# dac.net
KiCad netlist of a schematic drawn in EAGLE
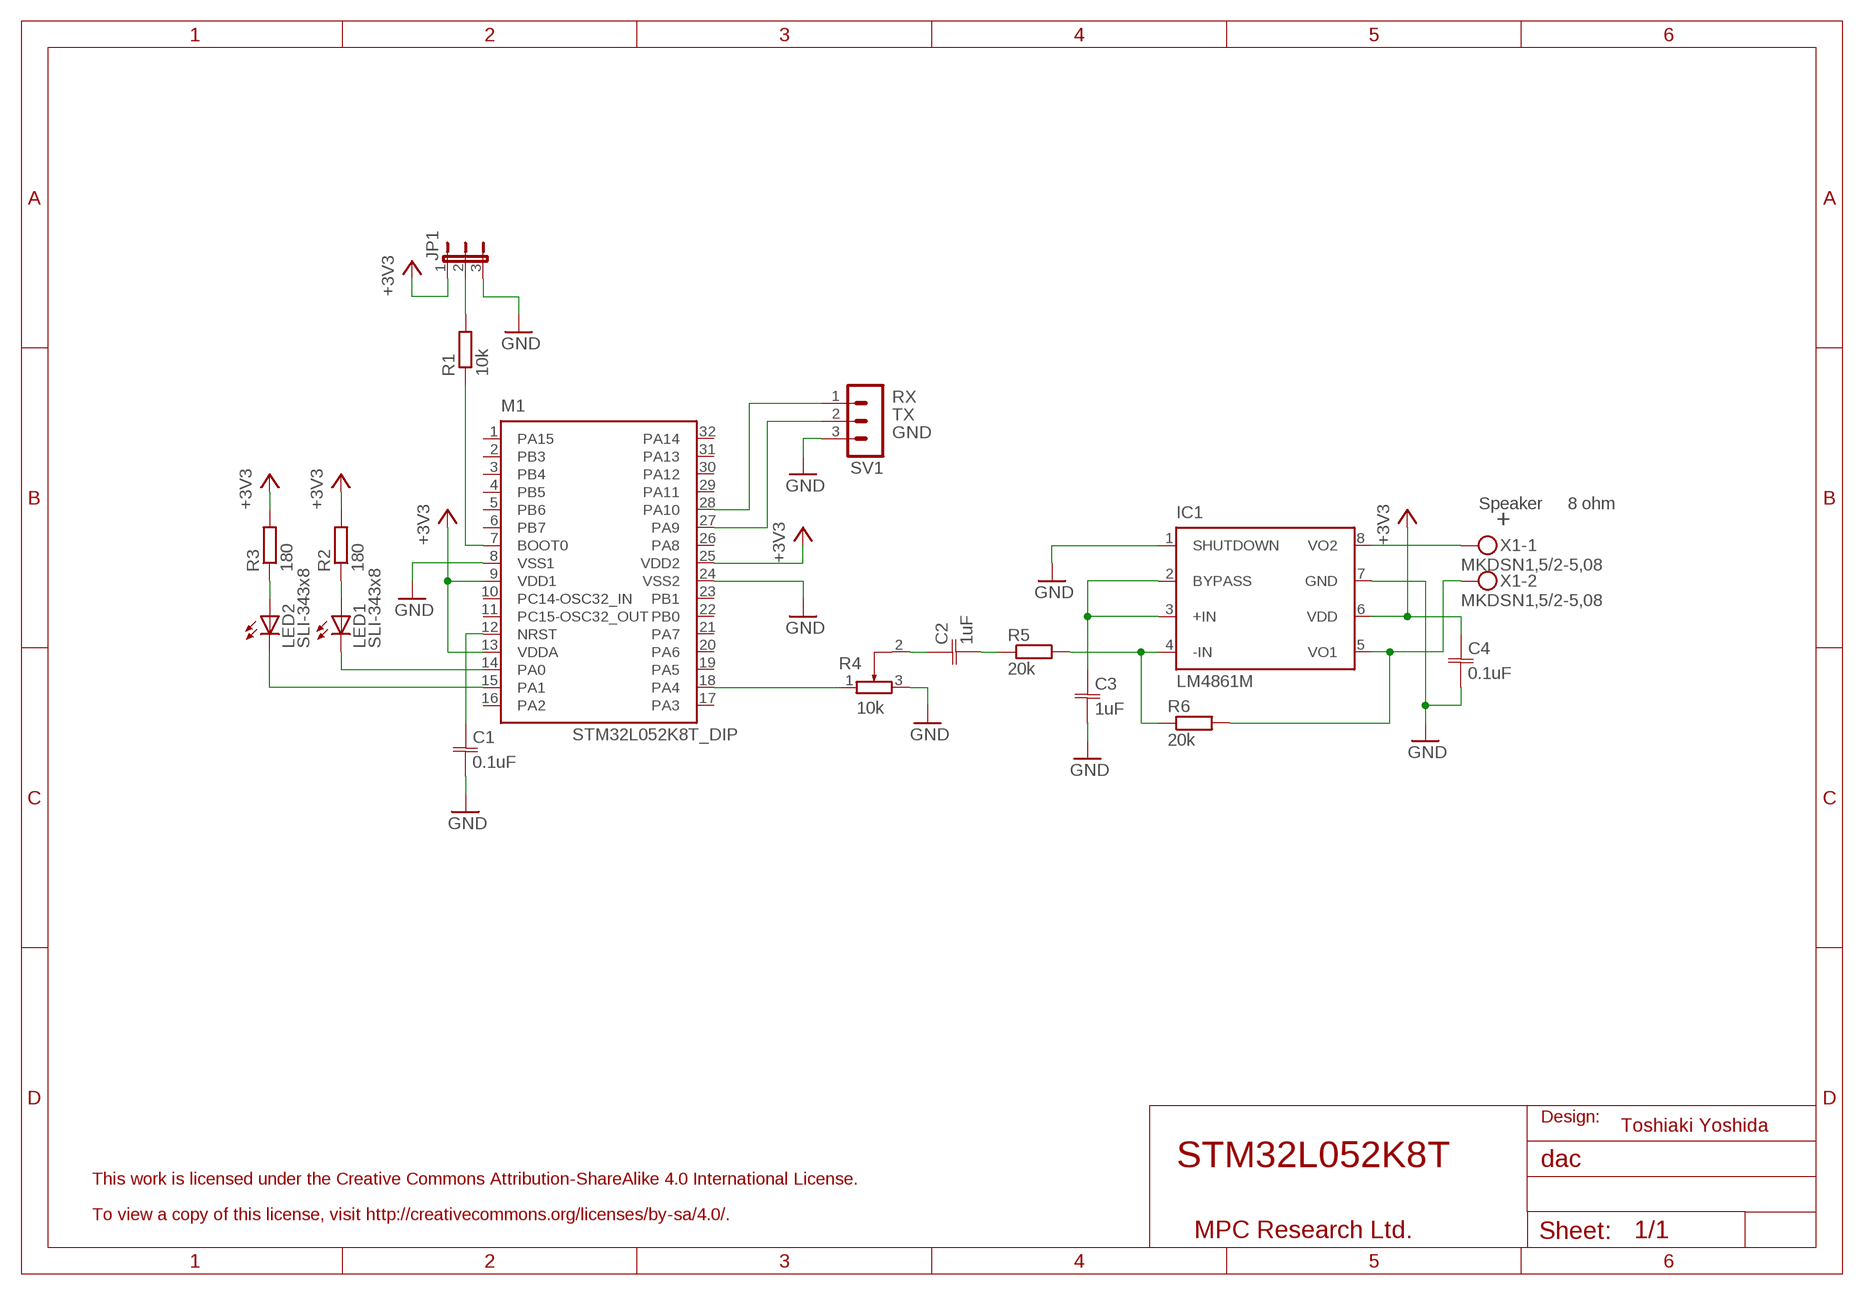
[diagram p0: schematic, sheet 1]

(export (version "E")
  (design (tool "Eeschema 10.0.6"))
  (components
    (comp (ref "C1")
      (value "0.1uF")
      (footprint "eagle-import:C050-024X044")
      (libsource (lib "eagle-import") (part "C-JIS050-024X044"))
    )
    (comp (ref "C2")
      (value "1uF")
      (footprint "eagle-import:C050-024X044")
      (libsource (lib "eagle-import") (part "C-JIS050-024X044"))
    )
    (comp (ref "C3")
      (value "1uF")
      (footprint "eagle-import:C050-024X044")
      (libsource (lib "eagle-import") (part "C-JIS050-024X044"))
    )
    (comp (ref "C4")
      (value "0.1uF")
      (footprint "eagle-import:C050-024X044")
      (libsource (lib "eagle-import") (part "C-JIS050-024X044"))
    )
    (comp (ref "IC1")
      (value "LM4861M")
      (footprint "eagle-import:SO-08")
      (libsource (lib "eagle-import") (part "LM4861M"))
    )
    (comp (ref "JP1")
      (value "JP2E")
      (footprint "eagle-import:JP2")
      (libsource (lib "eagle-import") (part "JP2E"))
    )
    (comp (ref "LED1")
      (value "SLI-343x8")
      (footprint "eagle-import:LED3MM")
      (libsource (lib "eagle-import") (part "LED3MM"))
    )
    (comp (ref "LED2")
      (value "SLI-343x8")
      (footprint "eagle-import:LED3MM")
      (libsource (lib "eagle-import") (part "LED3MM"))
    )
    (comp (ref "M1")
      (value "STM32L052K8T_DIP")
      (footprint "eagle-import:DIP32")
      (libsource (lib "eagle-import") (part "STM32L052K8T_DIP"))
    )
    (comp (ref "R1")
      (value "10k")
      (footprint "eagle-import:0207_2V")
      (libsource (lib "eagle-import") (part "R-EU_0207/2V"))
    )
    (comp (ref "R2")
      (value "180")
      (footprint "eagle-import:0207_2V")
      (libsource (lib "eagle-import") (part "R-EU_0207/2V"))
    )
    (comp (ref "R3")
      (value "180")
      (footprint "eagle-import:0207_2V")
      (libsource (lib "eagle-import") (part "R-EU_0207/2V"))
    )
    (comp (ref "R4")
      (value "10k")
      (footprint "eagle-import:TSR-3386T")
      (libsource (lib "eagle-import") (part "TSR-3386T-EY5"))
    )
    (comp (ref "R5")
      (value "20k")
      (footprint "eagle-import:0207_2V")
      (libsource (lib "eagle-import") (part "R-EU_0207/2V"))
    )
    (comp (ref "R6")
      (value "20k")
      (footprint "eagle-import:0207_10")
      (libsource (lib "eagle-import") (part "R-EU_0207/10"))
    )
    (comp (ref "SV1")
      (value "MA03-1")
      (footprint "eagle-import:MA03-1")
      (libsource (lib "eagle-import") (part "MA03-1"))
    )
    (comp (ref "X1")
      (value "MKDSN1,5/2-5,08")
      (footprint "eagle-import:MKDSN1,5_2-5,08")
      (libsource (lib "eagle-import") (part "MKDSN1,5/2-5,08"))
    )
  )
  (nets
    (net (code "1") (name "+3V3") (class "Default")
      (node (ref "C4") (pin "1") (pinfunction "1_1") (pintype "passive"))
      (node (ref "IC1") (pin "6") (pinfunction "VDD_6") (pintype "power_in"))
      (node (ref "JP1") (pin "1") (pinfunction "1_1") (pintype "passive"))
      (node (ref "M1") (pin "13") (pinfunction "VDDA_13") (pintype "power_in"))
      (node (ref "M1") (pin "25") (pinfunction "VDD2_25") (pintype "bidirectional"))
      (node (ref "M1") (pin "9") (pinfunction "VDD1_9") (pintype "power_in"))
      (node (ref "R2") (pin "2") (pinfunction "2_2") (pintype "passive"))
      (node (ref "R3") (pin "2") (pinfunction "2_2") (pintype "passive"))
    )
    (net (code "2") (name "GND") (class "Default")
      (node (ref "C1") (pin "2") (pinfunction "2_2") (pintype "passive"))
      (node (ref "C3") (pin "2") (pinfunction "2_2") (pintype "passive"))
      (node (ref "C4") (pin "2") (pinfunction "2_2") (pintype "passive"))
      (node (ref "IC1") (pin "1") (pinfunction "SHUTDOWN_1") (pintype "input"))
      (node (ref "IC1") (pin "7") (pinfunction "GND_7") (pintype "power_in"))
      (node (ref "JP1") (pin "3") (pinfunction "3_3") (pintype "passive"))
      (node (ref "M1") (pin "24") (pinfunction "VSS2_24") (pintype "power_in"))
      (node (ref "M1") (pin "8") (pinfunction "VSS1_8") (pintype "power_in"))
      (node (ref "R4") (pin "3") (pinfunction "3_3") (pintype "passive"))
      (node (ref "SV1") (pin "3") (pinfunction "3_3") (pintype "passive"))
    )
    (net (code "3") (name "Net-(C2-Pad1)") (class "Default")
      (node (ref "C2") (pin "1") (pinfunction "1_1") (pintype "passive"))
      (node (ref "R4") (pin "2") (pinfunction "2_2") (pintype "passive"))
    )
    (net (code "4") (name "Net-(C2-Pad2)") (class "Default")
      (node (ref "C2") (pin "2") (pinfunction "2_2") (pintype "passive"))
      (node (ref "R5") (pin "1") (pinfunction "1_1") (pintype "passive"))
    )
    (net (code "5") (name "Net-(IC1-+IN)") (class "Default")
      (node (ref "C3") (pin "1") (pinfunction "1_1") (pintype "passive"))
      (node (ref "IC1") (pin "2") (pinfunction "BYPASS_2") (pintype "passive"))
      (node (ref "IC1") (pin "3") (pinfunction "+IN_3") (pintype "input"))
    )
    (net (code "6") (name "Net-(IC1--IN)") (class "Default")
      (node (ref "IC1") (pin "4") (pinfunction "-IN_4") (pintype "input"))
      (node (ref "R5") (pin "2") (pinfunction "2_2") (pintype "passive"))
      (node (ref "R6") (pin "1") (pinfunction "1_1") (pintype "passive"))
    )
    (net (code "7") (name "Net-(IC1-VO1)") (class "Default")
      (node (ref "IC1") (pin "5") (pinfunction "VO1_5") (pintype "output"))
      (node (ref "R6") (pin "2") (pinfunction "2_2") (pintype "passive"))
      (node (ref "X1") (pin "2") (pinfunction "KL_2") (pintype "passive"))
    )
    (net (code "8") (name "Net-(IC1-VO2)") (class "Default")
      (node (ref "IC1") (pin "8") (pinfunction "VO2_8") (pintype "output"))
      (node (ref "X1") (pin "1") (pinfunction "KL_1") (pintype "passive"))
    )
    (net (code "9") (name "Net-(JP1-Pad2)") (class "Default")
      (node (ref "JP1") (pin "2") (pinfunction "2_2") (pintype "passive"))
      (node (ref "R1") (pin "2") (pinfunction "2_2") (pintype "passive"))
    )
    (net (code "10") (name "Net-(LED1-C)") (class "Default")
      (node (ref "LED1") (pin "K") (pinfunction "C_K") (pintype "passive"))
      (node (ref "M1") (pin "14") (pinfunction "PA0_14") (pintype "bidirectional"))
    )
    (net (code "11") (name "Net-(LED1-PadA)") (class "Default")
      (node (ref "LED1") (pin "A") (pinfunction "A_A") (pintype "passive"))
      (node (ref "R2") (pin "1") (pinfunction "1_1") (pintype "passive"))
    )
    (net (code "12") (name "Net-(LED2-C)") (class "Default")
      (node (ref "LED2") (pin "K") (pinfunction "C_K") (pintype "passive"))
      (node (ref "M1") (pin "15") (pinfunction "PA1_15") (pintype "bidirectional"))
    )
    (net (code "13") (name "Net-(LED2-PadA)") (class "Default")
      (node (ref "LED2") (pin "A") (pinfunction "A_A") (pintype "passive"))
      (node (ref "R3") (pin "1") (pinfunction "1_1") (pintype "passive"))
    )
    (net (code "14") (name "Net-(M1-BOOT0)") (class "Default")
      (node (ref "M1") (pin "7") (pinfunction "BOOT0_7") (pintype "bidirectional"))
      (node (ref "R1") (pin "1") (pinfunction "1_1") (pintype "passive"))
    )
    (net (code "15") (name "Net-(M1-NRST)") (class "Default")
      (node (ref "C1") (pin "1") (pinfunction "1_1") (pintype "passive"))
      (node (ref "M1") (pin "12") (pinfunction "NRST_12") (pintype "bidirectional"))
    )
    (net (code "16") (name "Net-(M1-PA4)") (class "Default")
      (node (ref "M1") (pin "18") (pinfunction "PA4_18") (pintype "bidirectional"))
      (node (ref "R4") (pin "1") (pinfunction "1_1") (pintype "passive"))
    )
    (net (code "17") (name "Net-(M1-PA9)") (class "Default")
      (node (ref "M1") (pin "27") (pinfunction "PA9_27") (pintype "bidirectional"))
      (node (ref "SV1") (pin "2") (pinfunction "2_2") (pintype "passive"))
    )
    (net (code "18") (name "Net-(M1-PA10)") (class "Default")
      (node (ref "M1") (pin "28") (pinfunction "PA10_28") (pintype "bidirectional"))
      (node (ref "SV1") (pin "1") (pinfunction "1_1") (pintype "passive"))
    )
    (net (code "19") (name "unconnected-(M1-PA2-Pad16)") (class "Default")
      (node (ref "M1") (pin "16") (pinfunction "PA2_16") (pintype "bidirectional"))
    )
    (net (code "20") (name "unconnected-(M1-PA3-Pad17)") (class "Default")
      (node (ref "M1") (pin "17") (pinfunction "PA3_17") (pintype "bidirectional"))
    )
    (net (code "21") (name "unconnected-(M1-PA5-Pad19)") (class "Default")
      (node (ref "M1") (pin "19") (pinfunction "PA5_19") (pintype "bidirectional"))
    )
    (net (code "22") (name "unconnected-(M1-PA6-Pad20)") (class "Default")
      (node (ref "M1") (pin "20") (pinfunction "PA6_20") (pintype "bidirectional"))
    )
    (net (code "23") (name "unconnected-(M1-PA7-Pad21)") (class "Default")
      (node (ref "M1") (pin "21") (pinfunction "PA7_21") (pintype "bidirectional"))
    )
    (net (code "24") (name "unconnected-(M1-PA8-Pad26)") (class "Default")
      (node (ref "M1") (pin "26") (pinfunction "PA8_26") (pintype "bidirectional"))
    )
    (net (code "25") (name "unconnected-(M1-PA11-Pad29)") (class "Default")
      (node (ref "M1") (pin "29") (pinfunction "PA11_29") (pintype "bidirectional"))
    )
    (net (code "26") (name "unconnected-(M1-PA12-Pad30)") (class "Default")
      (node (ref "M1") (pin "30") (pinfunction "PA12_30") (pintype "bidirectional"))
    )
    (net (code "27") (name "unconnected-(M1-PA13-Pad31)") (class "Default")
      (node (ref "M1") (pin "31") (pinfunction "PA13_31") (pintype "bidirectional"))
    )
    (net (code "28") (name "unconnected-(M1-PA14-Pad32)") (class "Default")
      (node (ref "M1") (pin "32") (pinfunction "PA14_32") (pintype "bidirectional"))
    )
    (net (code "29") (name "unconnected-(M1-PA15-Pad1)") (class "Default")
      (node (ref "M1") (pin "1") (pinfunction "PA15_1") (pintype "bidirectional"))
    )
    (net (code "30") (name "unconnected-(M1-PB0-Pad22)") (class "Default")
      (node (ref "M1") (pin "22") (pinfunction "PB0_22") (pintype "bidirectional"))
    )
    (net (code "31") (name "unconnected-(M1-PB1-Pad23)") (class "Default")
      (node (ref "M1") (pin "23") (pinfunction "PB1_23") (pintype "bidirectional"))
    )
    (net (code "32") (name "unconnected-(M1-PB3-Pad2)") (class "Default")
      (node (ref "M1") (pin "2") (pinfunction "PB3_2") (pintype "bidirectional"))
    )
    (net (code "33") (name "unconnected-(M1-PB4-Pad3)") (class "Default")
      (node (ref "M1") (pin "3") (pinfunction "PB4_3") (pintype "bidirectional"))
    )
    (net (code "34") (name "unconnected-(M1-PB5-Pad4)") (class "Default")
      (node (ref "M1") (pin "4") (pinfunction "PB5_4") (pintype "bidirectional"))
    )
    (net (code "35") (name "unconnected-(M1-PB6-Pad5)") (class "Default")
      (node (ref "M1") (pin "5") (pinfunction "PB6_5") (pintype "bidirectional"))
    )
    (net (code "36") (name "unconnected-(M1-PB7-Pad6)") (class "Default")
      (node (ref "M1") (pin "6") (pinfunction "PB7_6") (pintype "bidirectional"))
    )
    (net (code "37") (name "unconnected-(M1-PC14-OSC32_IN-Pad10)") (class "Default")
      (node (ref "M1") (pin "10") (pinfunction "PC14-OSC32_IN_10") (pintype "bidirectional"))
    )
    (net (code "38") (name "unconnected-(M1-PC15-OSC32_OUT-Pad11)") (class "Default")
      (node (ref "M1") (pin "11") (pinfunction "PC15-OSC32_OUT_11") (pintype "bidirectional"))
    )
  )
)
